# puzzlebot_schematics.net
KiCad netlist of a schematic drawn in EAGLE
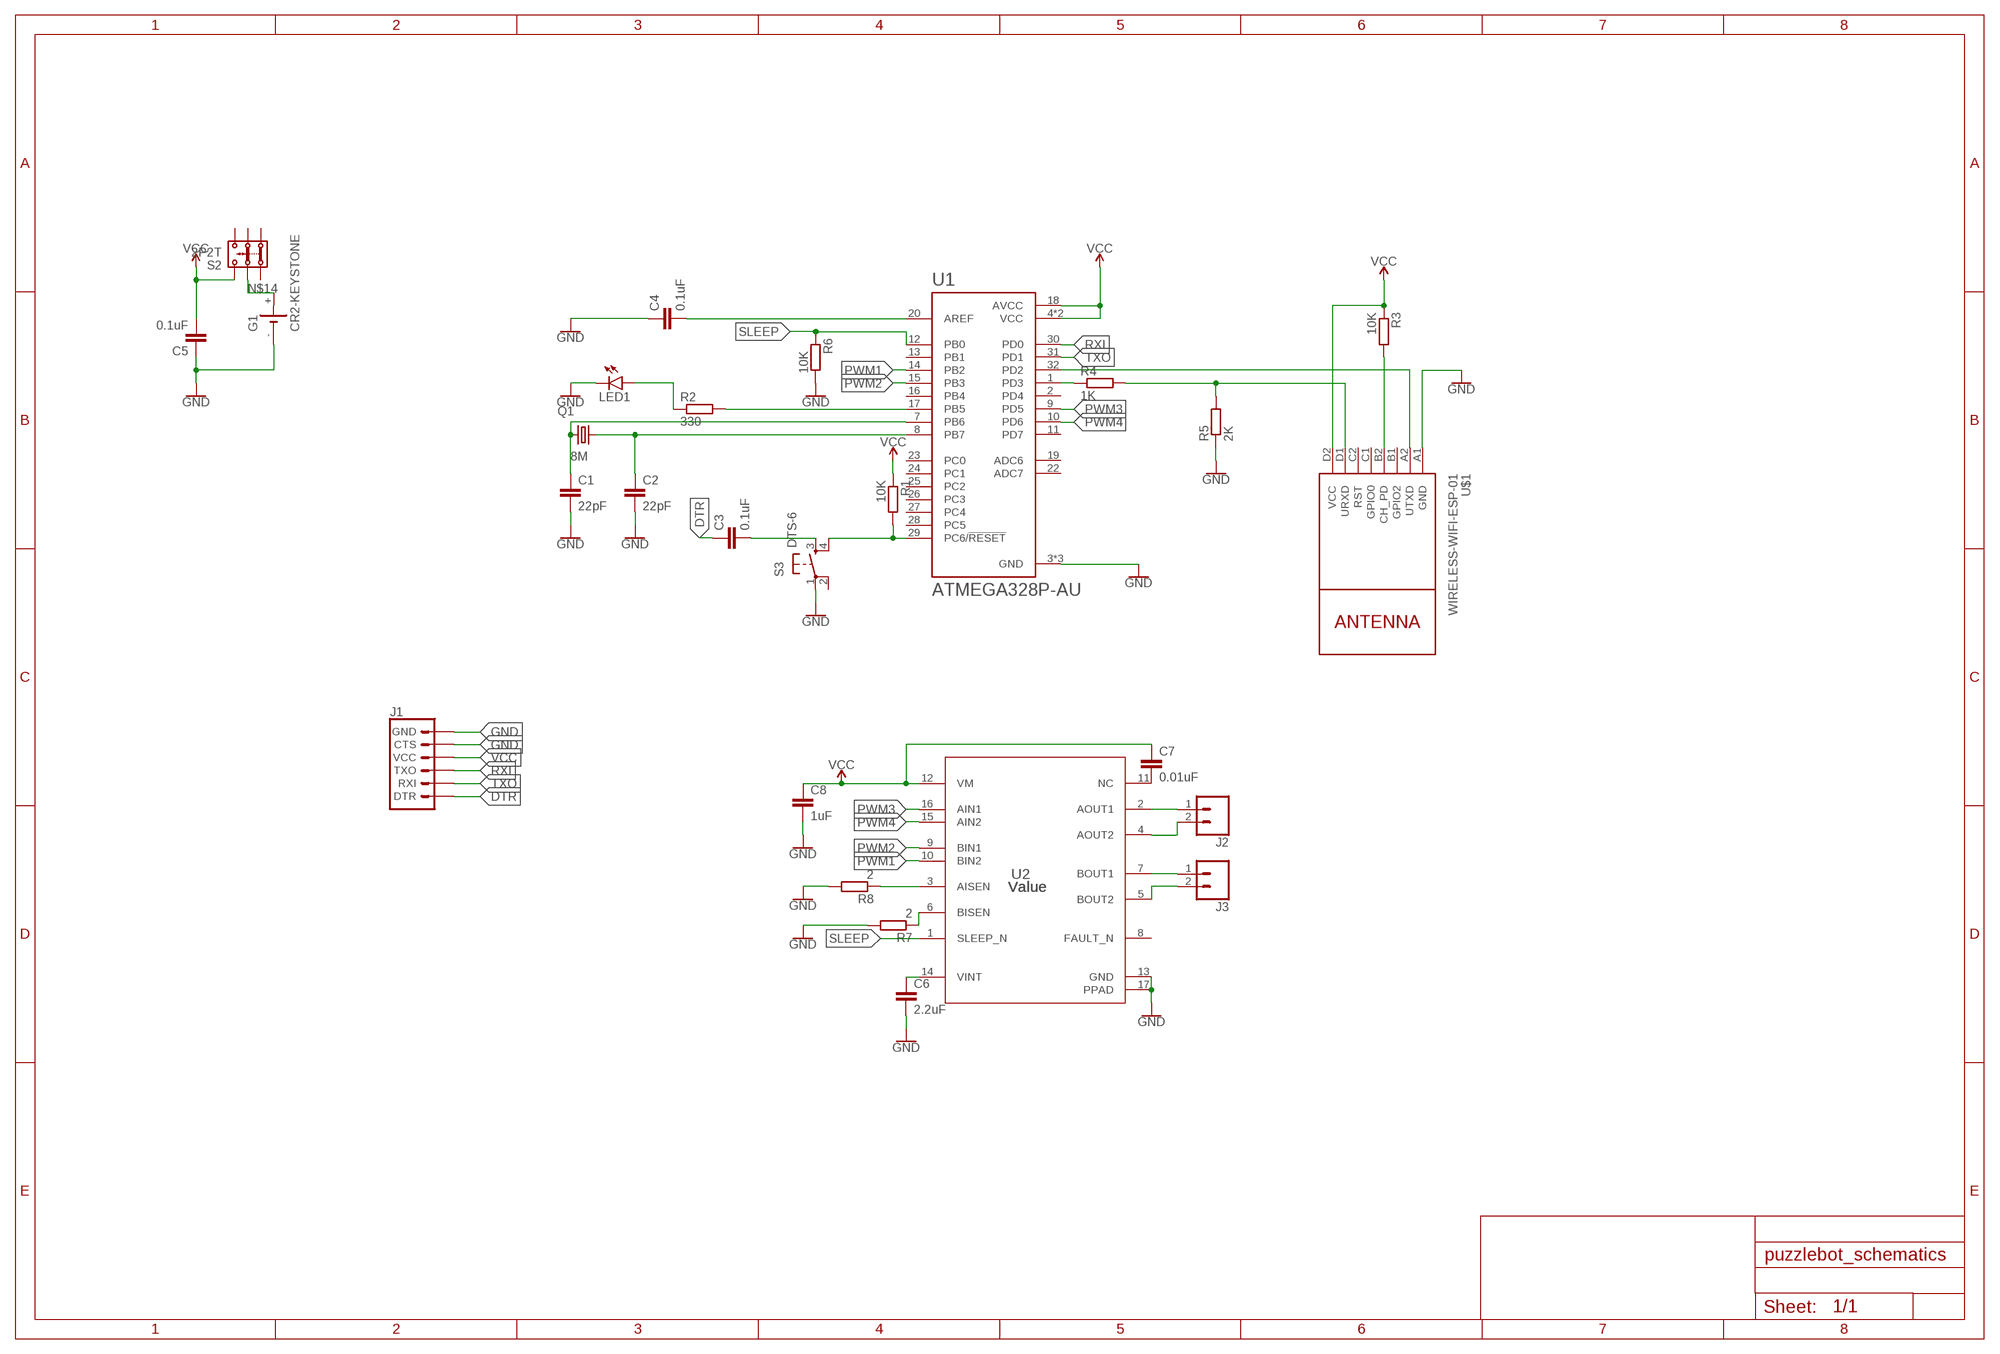
[diagram p0: schematic, sheet 1]

(export (version "E")
  (design (tool "Eeschema 10.0.6"))
  (components
    (comp (ref "C1")
      (value "22pF")
      (footprint "eagle-import:C0603")
      (libsource (lib "eagle-import") (part "C-EUC0603"))
    )
    (comp (ref "C2")
      (value "22pF")
      (footprint "eagle-import:C0603")
      (libsource (lib "eagle-import") (part "C-EUC0603"))
    )
    (comp (ref "C3")
      (value "0.1uF")
      (footprint "eagle-import:C0603")
      (libsource (lib "eagle-import") (part "C-EUC0603"))
    )
    (comp (ref "C4")
      (value "0.1uF")
      (footprint "eagle-import:C0603")
      (libsource (lib "eagle-import") (part "C-EUC0603"))
    )
    (comp (ref "C5")
      (value "0.1uF")
      (footprint "eagle-import:C0603")
      (libsource (lib "eagle-import") (part "C-EUC0603"))
    )
    (comp (ref "C6")
      (value "2.2uF")
      (footprint "eagle-import:C0603")
      (libsource (lib "eagle-import") (part "C-EUC0603"))
    )
    (comp (ref "C7")
      (value "0.01uF")
      (footprint "eagle-import:C0603")
      (libsource (lib "eagle-import") (part "C-EUC0603"))
    )
    (comp (ref "C8")
      (value "1uF")
      (footprint "eagle-import:C0603")
      (libsource (lib "eagle-import") (part "C-EUC0603"))
    )
    (comp (ref "G1")
      (value "CR2-KEYSTONE")
      (footprint "eagle-import:SL-150-1_2AA_PR")
      (libsource (lib "eagle-import") (part "CR2-KEYSTONE"))
    )
    (comp (ref "J1")
      (value "6_PIN_SERIAL_TARGETLONGPADS")
      (footprint "eagle-import:1X06_LONGPADS")
      (libsource (lib "eagle-import") (part "6_PIN_SERIAL_TARGETLONGPADS"))
    )
    (comp (ref "J2")
      (value "CONN_02POLAR")
      (footprint "eagle-import:MOLEX-1X2")
      (libsource (lib "eagle-import") (part "CONN_02POLAR"))
    )
    (comp (ref "J3")
      (value "CONN_02POLAR")
      (footprint "eagle-import:MOLEX-1X2")
      (libsource (lib "eagle-import") (part "CONN_02POLAR"))
    )
    (comp (ref "LED1")
      (value "LEDCHIP-LED0805")
      (footprint "eagle-import:CHIP-LED0805")
      (libsource (lib "eagle-import") (part "LEDCHIP-LED0805"))
    )
    (comp (ref "Q1")
      (value "8M")
      (footprint "eagle-import:CSM-7X-DU")
      (libsource (lib "eagle-import") (part "CSM-7X-DU"))
    )
    (comp (ref "R1")
      (value "10K")
      (footprint "eagle-import:R0603")
      (libsource (lib "eagle-import") (part "R-EU_R0603"))
    )
    (comp (ref "R2")
      (value "330")
      (footprint "eagle-import:R0603")
      (libsource (lib "eagle-import") (part "R-EU_R0603"))
    )
    (comp (ref "R3")
      (value "10K")
      (footprint "eagle-import:R0603")
      (libsource (lib "eagle-import") (part "R-EU_R0603"))
    )
    (comp (ref "R4")
      (value "1K")
      (footprint "eagle-import:R0603")
      (libsource (lib "eagle-import") (part "R-EU_R0603"))
    )
    (comp (ref "R5")
      (value "2K")
      (footprint "eagle-import:R0603")
      (libsource (lib "eagle-import") (part "R-EU_R0603"))
    )
    (comp (ref "R6")
      (value "10K")
      (footprint "eagle-import:R0603")
      (libsource (lib "eagle-import") (part "R-EU_R0603"))
    )
    (comp (ref "R7")
      (value "2")
      (footprint "eagle-import:R0603")
      (libsource (lib "eagle-import") (part "R-EU_R0603"))
    )
    (comp (ref "R8")
      (value "2")
      (footprint "eagle-import:R0603")
      (libsource (lib "eagle-import") (part "R-EU_R0603"))
    )
    (comp (ref "S2")
      (value "2P2T")
      (footprint "eagle-import:2P2T")
      (libsource (lib "eagle-import") (part "2P2T"))
    )
    (comp (ref "S3")
      (value "DTS-6")
      (footprint "eagle-import:DTS-6")
      (libsource (lib "eagle-import") (part "DTS-6"))
    )
    (comp (ref "U$1")
      (value "WIRELESS-WIFI-ESP-01")
      (footprint "eagle-import:WIRELESS-WIFI-ESP-01")
      (libsource (lib "eagle-import") (part "WIRELESS-WIFI-ESP-01"))
    )
    (comp (ref "U1")
      (value "ATMEGA328P-AU")
      (footprint "eagle-import:QFP80P900X900X120-32N")
      (fields (field (name "MF") "Microchip"))
      (libsource (lib "eagle-import") (part "ATMEGA328P-AU"))
    )
    (comp (ref "U2")
      (value "Value")
      (footprint "eagle-import:PWP0016K_M")
      (fields (field (name "MANUFACTURER") "Texas Instruments") (field (name "PARTNUMBER") "DRV8833CPWPR"))
      (libsource (lib "eagle-import") (part "DRV8833CPWPPWP0016K_M"))
    )
  )
  (nets
    (net (code "1") (name "/N$14") (class "Default")
      (node (ref "G1") (pin "+") (pinfunction "+_+") (pintype "passive"))
      (node (ref "S2") (pin "2.1") (pinfunction "2.1_2.1") (pintype "passive"))
    )
    (net (code "2") (name "DTR") (class "Default")
      (node (ref "C3") (pin "1") (pinfunction "1_1") (pintype "passive"))
      (node (ref "J1") (pin "1") (pinfunction "DTR_1") (pintype "passive"))
    )
    (net (code "3") (name "GND") (class "Default")
      (node (ref "C1") (pin "2") (pinfunction "2_2") (pintype "passive"))
      (node (ref "C2") (pin "2") (pinfunction "2_2") (pintype "passive"))
      (node (ref "C4") (pin "1") (pinfunction "1_1") (pintype "passive"))
      (node (ref "C5") (pin "1") (pinfunction "1_1") (pintype "passive"))
      (node (ref "C6") (pin "2") (pinfunction "2_2") (pintype "passive"))
      (node (ref "C8") (pin "2") (pinfunction "2_2") (pintype "passive"))
      (node (ref "G1") (pin "-") (pinfunction "-_-") (pintype "passive"))
      (node (ref "J1") (pin "5") (pinfunction "CTS_5") (pintype "passive"))
      (node (ref "J1") (pin "6") (pinfunction "GND_6") (pintype "passive"))
      (node (ref "LED1") (pin "C") (pinfunction "C_C") (pintype "passive"))
      (node (ref "R5") (pin "1") (pinfunction "1_1") (pintype "passive"))
      (node (ref "R6") (pin "2") (pinfunction "2_2") (pintype "passive"))
      (node (ref "R7") (pin "2") (pinfunction "2_2") (pintype "passive"))
      (node (ref "R8") (pin "2") (pinfunction "2_2") (pintype "passive"))
      (node (ref "S3") (pin "1") (pinfunction "1_1") (pintype "passive"))
      (node (ref "U$1") (pin "A1") (pinfunction "GND_A1") (pintype "power_in"))
      (node (ref "U1") (pin "21") (pinfunction "GND_21") (pintype "power_in"))
      (node (ref "U1") (pin "3") (pinfunction "GND_3") (pintype "power_in"))
      (node (ref "U1") (pin "5") (pinfunction "GND_5") (pintype "power_in"))
      (node (ref "U2") (pin "13") (pinfunction "GND_13") (pintype "power_in"))
      (node (ref "U2") (pin "17") (pinfunction "PPAD_17") (pintype "power_in"))
    )
    (net (code "4") (name "Net-(C3-Pad2)") (class "Default")
      (node (ref "C3") (pin "2") (pinfunction "2_2") (pintype "passive"))
      (node (ref "S3") (pin "3") (pinfunction "3_3") (pintype "passive"))
    )
    (net (code "5") (name "Net-(LED1-PadA)") (class "Default")
      (node (ref "LED1") (pin "A") (pinfunction "A_A") (pintype "passive"))
      (node (ref "R2") (pin "1") (pinfunction "1_1") (pintype "passive"))
    )
    (net (code "6") (name "Net-(U$1-CH_PD)") (class "Default")
      (node (ref "R3") (pin "2") (pinfunction "2_2") (pintype "passive"))
      (node (ref "U$1") (pin "B2") (pinfunction "CH_PD_B2") (pintype "bidirectional"))
    )
    (net (code "7") (name "Net-(U$1-URXD)") (class "Default")
      (node (ref "R4") (pin "2") (pinfunction "2_2") (pintype "passive"))
      (node (ref "R5") (pin "2") (pinfunction "2_2") (pintype "passive"))
      (node (ref "U$1") (pin "D1") (pinfunction "URXD_D1") (pintype "bidirectional"))
    )
    (net (code "8") (name "Net-(U$1-UTXD)") (class "Default")
      (node (ref "U$1") (pin "A2") (pinfunction "UTXD_A2") (pintype "bidirectional"))
      (node (ref "U1") (pin "32") (pinfunction "PD2_32") (pintype "bidirectional"))
    )
    (net (code "9") (name "Net-(U1-AREF)") (class "Default")
      (node (ref "C4") (pin "2") (pinfunction "2_2") (pintype "passive"))
      (node (ref "U1") (pin "20") (pinfunction "AREF_20") (pintype "input"))
    )
    (net (code "10") (name "Net-(U1-PB5)") (class "Default")
      (node (ref "R2") (pin "2") (pinfunction "2_2") (pintype "passive"))
      (node (ref "U1") (pin "17") (pinfunction "PB5_17") (pintype "bidirectional"))
    )
    (net (code "11") (name "Net-(U1-PB6)") (class "Default")
      (node (ref "C1") (pin "1") (pinfunction "1_1") (pintype "passive"))
      (node (ref "Q1") (pin "1") (pinfunction "1_1") (pintype "passive"))
      (node (ref "U1") (pin "7") (pinfunction "PB6_7") (pintype "bidirectional"))
    )
    (net (code "12") (name "Net-(U1-PB7)") (class "Default")
      (node (ref "C2") (pin "1") (pinfunction "1_1") (pintype "passive"))
      (node (ref "Q1") (pin "2") (pinfunction "2_2") (pintype "passive"))
      (node (ref "U1") (pin "8") (pinfunction "PB7_8") (pintype "bidirectional"))
    )
    (net (code "13") (name "Net-(U1-PC6{slash}~{RESET})") (class "Default")
      (node (ref "R1") (pin "2") (pinfunction "2_2") (pintype "passive"))
      (node (ref "S3") (pin "4") (pinfunction "4_4") (pintype "passive"))
      (node (ref "U1") (pin "29") (pinfunction "PC6/~{RESET}_29") (pintype "bidirectional"))
    )
    (net (code "14") (name "Net-(U1-PD3)") (class "Default")
      (node (ref "R4") (pin "1") (pinfunction "1_1") (pintype "passive"))
      (node (ref "U1") (pin "1") (pinfunction "PD3_1") (pintype "bidirectional"))
    )
    (net (code "15") (name "Net-(U2-AISEN)") (class "Default")
      (node (ref "R8") (pin "1") (pinfunction "1_1") (pintype "passive"))
      (node (ref "U2") (pin "3") (pinfunction "AISEN_3") (pintype "input"))
    )
    (net (code "16") (name "Net-(U2-AOUT1)") (class "Default")
      (node (ref "J2") (pin "1") (pinfunction "1_1") (pintype "passive"))
      (node (ref "U2") (pin "2") (pinfunction "AOUT1_2") (pintype "tri_state"))
    )
    (net (code "17") (name "Net-(U2-AOUT2)") (class "Default")
      (node (ref "J2") (pin "2") (pinfunction "2_2") (pintype "passive"))
      (node (ref "U2") (pin "4") (pinfunction "AOUT2_4") (pintype "tri_state"))
    )
    (net (code "18") (name "Net-(U2-BISEN)") (class "Default")
      (node (ref "R7") (pin "1") (pinfunction "1_1") (pintype "passive"))
      (node (ref "U2") (pin "6") (pinfunction "BISEN_6") (pintype "input"))
    )
    (net (code "19") (name "Net-(U2-BOUT1)") (class "Default")
      (node (ref "J3") (pin "1") (pinfunction "1_1") (pintype "passive"))
      (node (ref "U2") (pin "7") (pinfunction "BOUT1_7") (pintype "tri_state"))
    )
    (net (code "20") (name "Net-(U2-BOUT2)") (class "Default")
      (node (ref "J3") (pin "2") (pinfunction "2_2") (pintype "passive"))
      (node (ref "U2") (pin "5") (pinfunction "BOUT2_5") (pintype "tri_state"))
    )
    (net (code "21") (name "Net-(U2-NC)") (class "Default")
      (node (ref "C7") (pin "2") (pinfunction "2_2") (pintype "passive"))
      (node (ref "U2") (pin "11") (pinfunction "NC_11") (pintype "passive"))
    )
    (net (code "22") (name "Net-(U2-VINT)") (class "Default")
      (node (ref "C6") (pin "1") (pinfunction "1_1") (pintype "passive"))
      (node (ref "U2") (pin "14") (pinfunction "VINT_14") (pintype "passive"))
    )
    (net (code "23") (name "PWM1") (class "Default")
      (node (ref "U1") (pin "14") (pinfunction "PB2_14") (pintype "bidirectional"))
      (node (ref "U2") (pin "10") (pinfunction "BIN2_10") (pintype "input"))
    )
    (net (code "24") (name "PWM2") (class "Default")
      (node (ref "U1") (pin "15") (pinfunction "PB3_15") (pintype "bidirectional"))
      (node (ref "U2") (pin "9") (pinfunction "BIN1_9") (pintype "input"))
    )
    (net (code "25") (name "PWM3") (class "Default")
      (node (ref "U1") (pin "9") (pinfunction "PD5_9") (pintype "bidirectional"))
      (node (ref "U2") (pin "16") (pinfunction "AIN1_16") (pintype "input"))
    )
    (net (code "26") (name "PWM4") (class "Default")
      (node (ref "U1") (pin "10") (pinfunction "PD6_10") (pintype "bidirectional"))
      (node (ref "U2") (pin "15") (pinfunction "AIN2_15") (pintype "input"))
    )
    (net (code "27") (name "RXI") (class "Default")
      (node (ref "J1") (pin "3") (pinfunction "TXO_3") (pintype "passive"))
      (node (ref "U1") (pin "30") (pinfunction "PD0_30") (pintype "bidirectional"))
    )
    (net (code "28") (name "SLEEP") (class "Default")
      (node (ref "R6") (pin "1") (pinfunction "1_1") (pintype "passive"))
      (node (ref "U1") (pin "12") (pinfunction "PB0_12") (pintype "bidirectional"))
      (node (ref "U2") (pin "1") (pinfunction "SLEEP_N_1") (pintype "input"))
    )
    (net (code "29") (name "TXO") (class "Default")
      (node (ref "J1") (pin "2") (pinfunction "RXI_2") (pintype "passive"))
      (node (ref "U1") (pin "31") (pinfunction "PD1_31") (pintype "bidirectional"))
    )
    (net (code "30") (name "VCC") (class "Default")
      (node (ref "C5") (pin "2") (pinfunction "2_2") (pintype "passive"))
      (node (ref "C7") (pin "1") (pinfunction "1_1") (pintype "passive"))
      (node (ref "C8") (pin "1") (pinfunction "1_1") (pintype "passive"))
      (node (ref "J1") (pin "4") (pinfunction "VCC_4") (pintype "passive"))
      (node (ref "R1") (pin "1") (pinfunction "1_1") (pintype "passive"))
      (node (ref "R3") (pin "1") (pinfunction "1_1") (pintype "passive"))
      (node (ref "S2") (pin "3.1") (pinfunction "3.1_3.1") (pintype "passive"))
      (node (ref "U$1") (pin "D2") (pinfunction "VCC_D2") (pintype "power_in"))
      (node (ref "U1") (pin "18") (pinfunction "AVCC_18") (pintype "power_in"))
      (node (ref "U1") (pin "4") (pinfunction "VCC_4") (pintype "power_in"))
      (node (ref "U1") (pin "6") (pinfunction "VCC_6") (pintype "power_in"))
      (node (ref "U2") (pin "12") (pinfunction "VM_12") (pintype "power_in"))
    )
    (net (code "31") (name "unconnected-(S2-Pad1.1)") (class "Default")
      (node (ref "S2") (pin "1.1") (pinfunction "1.1_1.1") (pintype "passive"))
    )
    (net (code "32") (name "unconnected-(S2-Pad1.2)") (class "Default")
      (node (ref "S2") (pin "1.2") (pinfunction "1.2_1.2") (pintype "passive"))
    )
    (net (code "33") (name "unconnected-(S2-Pad2.2)") (class "Default")
      (node (ref "S2") (pin "2.2") (pinfunction "2.2_2.2") (pintype "passive"))
    )
    (net (code "34") (name "unconnected-(S2-Pad3.2)") (class "Default")
      (node (ref "S2") (pin "3.2") (pinfunction "3.2_3.2") (pintype "passive"))
    )
    (net (code "35") (name "unconnected-(S3-Pad2)") (class "Default")
      (node (ref "S3") (pin "2") (pinfunction "2_2") (pintype "passive"))
    )
    (net (code "36") (name "unconnected-(U$1-GPIO0-PadC1)") (class "Default")
      (node (ref "U$1") (pin "C1") (pinfunction "GPIO0_C1") (pintype "bidirectional"))
    )
    (net (code "37") (name "unconnected-(U$1-GPIO2-PadB1)") (class "Default")
      (node (ref "U$1") (pin "B1") (pinfunction "GPIO2_B1") (pintype "bidirectional"))
    )
    (net (code "38") (name "unconnected-(U$1-RST-PadC2)") (class "Default")
      (node (ref "U$1") (pin "C2") (pinfunction "RST_C2") (pintype "bidirectional"))
    )
    (net (code "39") (name "unconnected-(U1-ADC6-Pad19)") (class "Default")
      (node (ref "U1") (pin "19") (pinfunction "ADC6_19") (pintype "bidirectional"))
    )
    (net (code "40") (name "unconnected-(U1-ADC7-Pad22)") (class "Default")
      (node (ref "U1") (pin "22") (pinfunction "ADC7_22") (pintype "bidirectional"))
    )
    (net (code "41") (name "unconnected-(U1-PB1-Pad13)") (class "Default")
      (node (ref "U1") (pin "13") (pinfunction "PB1_13") (pintype "bidirectional"))
    )
    (net (code "42") (name "unconnected-(U1-PB4-Pad16)") (class "Default")
      (node (ref "U1") (pin "16") (pinfunction "PB4_16") (pintype "bidirectional"))
    )
    (net (code "43") (name "unconnected-(U1-PC0-Pad23)") (class "Default")
      (node (ref "U1") (pin "23") (pinfunction "PC0_23") (pintype "bidirectional"))
    )
    (net (code "44") (name "unconnected-(U1-PC1-Pad24)") (class "Default")
      (node (ref "U1") (pin "24") (pinfunction "PC1_24") (pintype "bidirectional"))
    )
    (net (code "45") (name "unconnected-(U1-PC2-Pad25)") (class "Default")
      (node (ref "U1") (pin "25") (pinfunction "PC2_25") (pintype "bidirectional"))
    )
    (net (code "46") (name "unconnected-(U1-PC3-Pad26)") (class "Default")
      (node (ref "U1") (pin "26") (pinfunction "PC3_26") (pintype "bidirectional"))
    )
    (net (code "47") (name "unconnected-(U1-PC4-Pad27)") (class "Default")
      (node (ref "U1") (pin "27") (pinfunction "PC4_27") (pintype "bidirectional"))
    )
    (net (code "48") (name "unconnected-(U1-PC5-Pad28)") (class "Default")
      (node (ref "U1") (pin "28") (pinfunction "PC5_28") (pintype "bidirectional"))
    )
    (net (code "49") (name "unconnected-(U1-PD4-Pad2)") (class "Default")
      (node (ref "U1") (pin "2") (pinfunction "PD4_2") (pintype "bidirectional"))
    )
    (net (code "50") (name "unconnected-(U1-PD7-Pad11)") (class "Default")
      (node (ref "U1") (pin "11") (pinfunction "PD7_11") (pintype "bidirectional"))
    )
    (net (code "51") (name "unconnected-(U2-FAULT_N-Pad8)") (class "Default")
      (node (ref "U2") (pin "8") (pinfunction "FAULT_N_8") (pintype "open_collector"))
    )
  )
)
